# Base_4node_V2_0.net
KiCad netlist of a schematic drawn in EAGLE
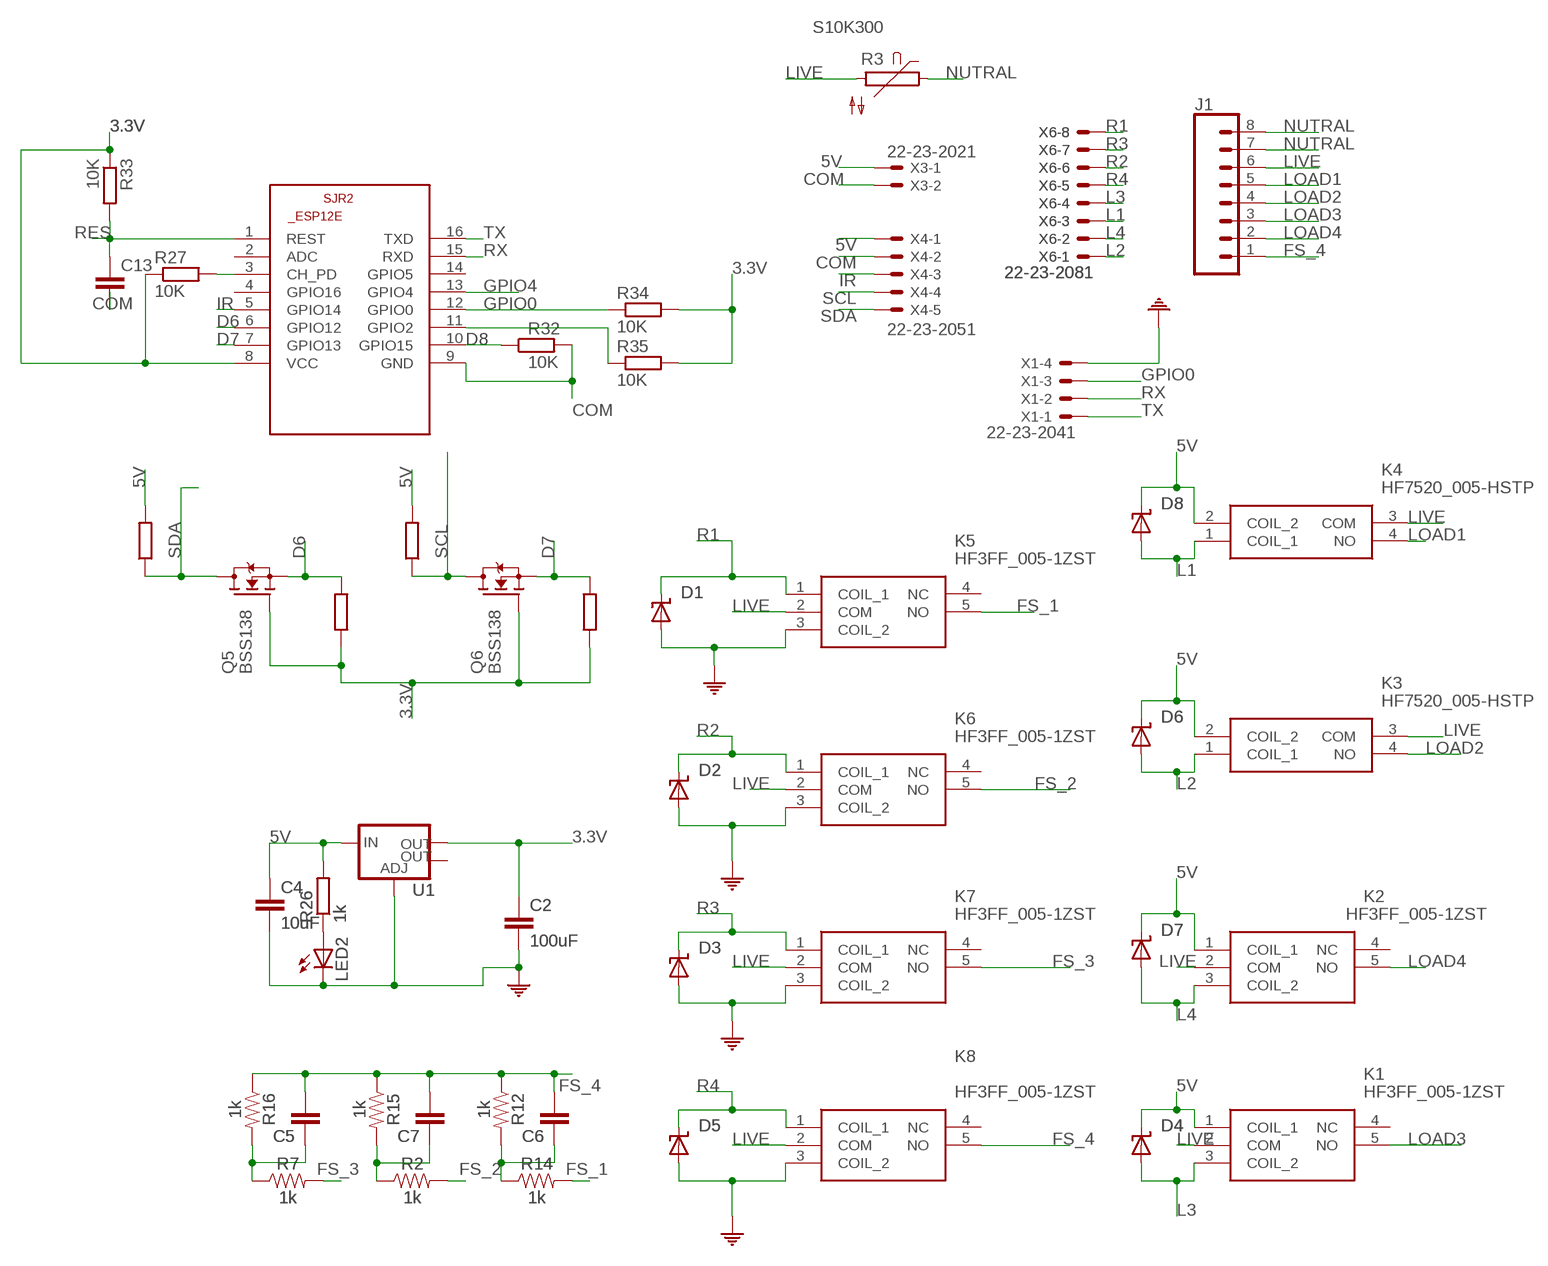
[diagram p0: schematic, sheet 1]

(export (version "E")
  (design (tool "Eeschema 10.0.6"))
  (components
    (comp (ref "C2")
      (value "100uF")
      (footprint "eagle-import:C1206")
      (libsource (lib "eagle-import") (part "C-EUC1206"))
    )
    (comp (ref "C4")
      (value "10uF")
      (footprint "eagle-import:C1206")
      (libsource (lib "eagle-import") (part "C-EUC1206"))
    )
    (comp (ref "C5")
      (value "C-EU275-134X316")
      (footprint "eagle-import:C275-134X316")
      (libsource (lib "eagle-import") (part "C-EU275-134X316"))
    )
    (comp (ref "C6")
      (value "C-EU275-093X316")
      (footprint "eagle-import:C275-093X316")
      (libsource (lib "eagle-import") (part "rcl-2_C-EU275-093X316"))
    )
    (comp (ref "C7")
      (value "C-EU275-113X316")
      (footprint "eagle-import:C275-113X316")
      (libsource (lib "eagle-import") (part "rcl-2_C-EU275-113X316"))
    )
    (comp (ref "C13")
      (value "C-EUC0805")
      (footprint "eagle-import:C0805")
      (libsource (lib "eagle-import") (part "rcl_334_C-EUC0805"))
    )
    (comp (ref "D1")
      (value "SUPPRESSOR-SMBJ")
      (footprint "eagle-import:SMBJ")
      (libsource (lib "eagle-import") (part "SUPPRESSOR-SMBJ"))
    )
    (comp (ref "D2")
      (value "SUPPRESSOR-SMBJ")
      (footprint "eagle-import:SMBJ")
      (libsource (lib "eagle-import") (part "SUPPRESSOR-SMBJ"))
    )
    (comp (ref "D3")
      (value "SUPPRESSOR-SMBJ")
      (footprint "eagle-import:SMBJ")
      (libsource (lib "eagle-import") (part "SUPPRESSOR-SMBJ"))
    )
    (comp (ref "D4")
      (value "SUPPRESSOR-SMBJ")
      (footprint "eagle-import:SMBJ")
      (libsource (lib "eagle-import") (part "SUPPRESSOR-SMBJ"))
    )
    (comp (ref "D5")
      (value "SUPPRESSOR-SMBJ")
      (footprint "eagle-import:SMBJ")
      (libsource (lib "eagle-import") (part "SUPPRESSOR-SMBJ"))
    )
    (comp (ref "D6")
      (value "SUPPRESSOR-SMBJ")
      (footprint "eagle-import:SMBJ")
      (libsource (lib "eagle-import") (part "SUPPRESSOR-SMBJ"))
    )
    (comp (ref "D7")
      (value "SUPPRESSOR-SMBJ")
      (footprint "eagle-import:SMBJ")
      (libsource (lib "eagle-import") (part "SUPPRESSOR-SMBJ"))
    )
    (comp (ref "D8")
      (value "SUPPRESSOR-SMBJ")
      (footprint "eagle-import:SMBJ")
      (libsource (lib "eagle-import") (part "SUPPRESSOR-SMBJ"))
    )
    (comp (ref "J1")
      (value "CONN_083.5MM-8")
      (footprint "eagle-import:SCREWTERMINAL-3.5MM-8")
      (libsource (lib "eagle-import") (part "CONN_083.5MM-8"))
    )
    (comp (ref "K1")
      (value "HF3FF_005-1ZST")
      (footprint "eagle-import:HF3FF0051ZST")
      (fields (field (name "ARROW_PART_NUMBER") "HF3FF/005-1ZST"))
      (libsource (lib "eagle-import") (part "HF3FF_005-1ZST"))
    )
    (comp (ref "K2")
      (value "HF3FF_005-1ZST")
      (footprint "eagle-import:HF3FF0051ZST")
      (fields (field (name "ARROW_PART_NUMBER") "HF3FF/005-1ZST"))
      (libsource (lib "eagle-import") (part "HF3FF_005-1ZST"))
    )
    (comp (ref "K3")
      (value "HF7520_005-HSTP")
      (footprint "eagle-import:HF7520005HSTP")
      (fields (field (name "ARROW_PART_NUMBER") "HF7520/005-HSTP"))
      (libsource (lib "eagle-import") (part "HF7520_005-HSTP"))
    )
    (comp (ref "K4")
      (value "HF7520_005-HSTP")
      (footprint "eagle-import:HF7520005HSTP")
      (fields (field (name "ARROW_PART_NUMBER") "HF7520/005-HSTP"))
      (libsource (lib "eagle-import") (part "HF7520_005-HSTP"))
    )
    (comp (ref "K5")
      (value "HF3FF_005-1ZST")
      (footprint "eagle-import:HF3FF0051ZST")
      (fields (field (name "ARROW_PART_NUMBER") "HF3FF/005-1ZST"))
      (libsource (lib "eagle-import") (part "HF3FF_005-1ZST"))
    )
    (comp (ref "K6")
      (value "HF3FF_005-1ZST")
      (footprint "eagle-import:HF3FF0051ZST")
      (fields (field (name "ARROW_PART_NUMBER") "HF3FF/005-1ZST"))
      (libsource (lib "eagle-import") (part "HF3FF_005-1ZST"))
    )
    (comp (ref "K7")
      (value "HF3FF_005-1ZST")
      (footprint "eagle-import:HF3FF0051ZST")
      (fields (field (name "ARROW_PART_NUMBER") "HF3FF/005-1ZST"))
      (libsource (lib "eagle-import") (part "HF3FF_005-1ZST"))
    )
    (comp (ref "K8")
      (value "HF3FF_005-1ZST")
      (footprint "eagle-import:HF3FF0051ZST")
      (fields (field (name "ARROW_PART_NUMBER") "HF3FF/005-1ZST"))
      (libsource (lib "eagle-import") (part "HF3FF_005-1ZST"))
    )
    (comp (ref "LED2")
      (value "LEDCHIPLED_1206")
      (footprint "eagle-import:CHIPLED_1206")
      (libsource (lib "eagle-import") (part "LEDCHIPLED_1206"))
    )
    (comp (ref "Q5")
      (value "BSS138")
      (footprint "eagle-import:SOT23")
      (fields (field (name "MF") "Fairchild"))
      (libsource (lib "eagle-import") (part "BSS138"))
    )
    (comp (ref "Q6")
      (value "BSS138")
      (footprint "eagle-import:SOT23")
      (fields (field (name "MF") "Fairchild"))
      (libsource (lib "eagle-import") (part "BSS138"))
    )
    (comp (ref "R2")
      (value "1k")
      (footprint "eagle-import:AXIAL-0.1")
      (libsource (lib "eagle-import") (part "1KOHM-VERT-1/4W-1%"))
    )
    (comp (ref "R3")
      (value "S10K300")
      (footprint "eagle-import:S10K300")
      (libsource (lib "eagle-import") (part "S10K300"))
    )
    (comp (ref "R7")
      (value "1k")
      (footprint "eagle-import:AXIAL-0.1")
      (libsource (lib "eagle-import") (part "1KOHM-VERT-1/4W-1%"))
    )
    (comp (ref "R12")
      (value "1k")
      (footprint "eagle-import:AXIAL-0.3")
      (libsource (lib "eagle-import") (part "SparkFun-Resistors1_1KOHM-HORIZ-1/4W-1%"))
    )
    (comp (ref "R14")
      (value "1k")
      (footprint "eagle-import:AXIAL-0.1")
      (libsource (lib "eagle-import") (part "1KOHM-VERT-1/4W-1%"))
    )
    (comp (ref "R15")
      (value "1k")
      (footprint "eagle-import:AXIAL-0.3")
      (libsource (lib "eagle-import") (part "SparkFun-Resistors1_1KOHM-HORIZ-1/4W-1%"))
    )
    (comp (ref "R16")
      (value "1k")
      (footprint "eagle-import:AXIAL-0.3")
      (libsource (lib "eagle-import") (part "SparkFun-Resistors1_1KOHM-HORIZ-1/4W-1%"))
    )
    (comp (ref "R26")
      (value "1k")
      (footprint "eagle-import:R0805")
      (libsource (lib "eagle-import") (part "R-EU_R0805"))
    )
    (comp (ref "R27")
      (value "10K")
      (footprint "eagle-import:R0805")
      (libsource (lib "eagle-import") (part "resistor_348_R-EU_R0805"))
    )
    (comp (ref "R32")
      (value "10K")
      (footprint "eagle-import:R0805")
      (libsource (lib "eagle-import") (part "resistor_348_R-EU_R0805"))
    )
    (comp (ref "R33")
      (value "10K")
      (footprint "eagle-import:R0805")
      (libsource (lib "eagle-import") (part "resistor_348_R-EU_R0805"))
    )
    (comp (ref "R34")
      (value "10K")
      (footprint "eagle-import:R0805")
      (libsource (lib "eagle-import") (part "resistor_348_R-EU_R0805"))
    )
    (comp (ref "R35")
      (value "10K")
      (footprint "eagle-import:R0805")
      (libsource (lib "eagle-import") (part "resistor_348_R-EU_R0805"))
    )
    (comp (ref "R36")
      (value "10K")
      (footprint "eagle-import:R0805")
      (libsource (lib "eagle-import") (part "resistor_348_R-EU_R0805"))
    )
    (comp (ref "R37")
      (value "10K")
      (footprint "eagle-import:R0805")
      (libsource (lib "eagle-import") (part "resistor_348_R-EU_R0805"))
    )
    (comp (ref "R38")
      (value "10K")
      (footprint "eagle-import:R0805")
      (libsource (lib "eagle-import") (part "resistor_348_R-EU_R0805"))
    )
    (comp (ref "R39")
      (value "10K")
      (footprint "eagle-import:R0805")
      (libsource (lib "eagle-import") (part "resistor_348_R-EU_R0805"))
    )
    (comp (ref "SJR2")
      (value "ESP8266-12EESP12E")
      (footprint "eagle-import:ESP8266-ESP12E")
      (libsource (lib "eagle-import") (part "ESP8266-12EESP12E"))
    )
    (comp (ref "U1")
      (value "V_REG_LM1117SOT223")
      (footprint "eagle-import:SOT223")
      (libsource (lib "eagle-import") (part "V_REG_LM1117SOT223"))
    )
    (comp (ref "X1")
      (value "22-23-2041")
      (footprint "eagle-import:22-23-2041")
      (libsource (lib "eagle-import") (part "22-23-2041"))
    )
    (comp (ref "X3")
      (value "22-23-2021")
      (footprint "eagle-import:22-23-2021")
      (libsource (lib "eagle-import") (part "22-23-2021"))
    )
    (comp (ref "X4")
      (value "22-23-2051")
      (footprint "eagle-import:22-23-2051")
      (libsource (lib "eagle-import") (part "22-23-2051"))
    )
    (comp (ref "X6")
      (value "22-23-2081")
      (footprint "eagle-import:22-23-2081")
      (libsource (lib "eagle-import") (part "22-23-2081"))
    )
  )
  (nets
    (net (code "1") (name "/3.3V") (class "Default")
      (node (ref "C2") (pin "1") (pinfunction "1_1") (pintype "passive"))
      (node (ref "Q5") (pin "1") (pinfunction "G_1") (pintype "passive"))
      (node (ref "Q6") (pin "1") (pinfunction "G_1") (pintype "passive"))
      (node (ref "R27") (pin "1") (pinfunction "1_1") (pintype "passive"))
      (node (ref "R33") (pin "1") (pinfunction "1_1") (pintype "passive"))
      (node (ref "R34") (pin "2") (pinfunction "2_2") (pintype "passive"))
      (node (ref "R35") (pin "2") (pinfunction "2_2") (pintype "passive"))
      (node (ref "R37") (pin "2") (pinfunction "2_2") (pintype "passive"))
      (node (ref "R39") (pin "2") (pinfunction "2_2") (pintype "passive"))
      (node (ref "SJR2") (pin "8") (pinfunction "VCC_8") (pintype "bidirectional"))
      (node (ref "U1") (pin "2") (pinfunction "OUT_2") (pintype "output"))
    )
    (net (code "2") (name "/5V") (class "Default")
      (node (ref "C4") (pin "1") (pinfunction "1_1") (pintype "passive"))
      (node (ref "D4") (pin "C") (pinfunction "C_C") (pintype "passive"))
      (node (ref "D6") (pin "C") (pinfunction "C_C") (pintype "passive"))
      (node (ref "D7") (pin "C") (pinfunction "C_C") (pintype "passive"))
      (node (ref "D8") (pin "C") (pinfunction "C_C") (pintype "passive"))
      (node (ref "K1") (pin "1") (pinfunction "COIL_1_1") (pintype "bidirectional"))
      (node (ref "K2") (pin "1") (pinfunction "COIL_1_1") (pintype "bidirectional"))
      (node (ref "K3") (pin "2") (pinfunction "COIL_2_2") (pintype "bidirectional"))
      (node (ref "K4") (pin "2") (pinfunction "COIL_2_2") (pintype "bidirectional"))
      (node (ref "R26") (pin "2") (pinfunction "2_2") (pintype "passive"))
      (node (ref "R36") (pin "2") (pinfunction "2_2") (pintype "passive"))
      (node (ref "R38") (pin "2") (pinfunction "2_2") (pintype "passive"))
      (node (ref "U1") (pin "3") (pinfunction "IN_3") (pintype "input"))
      (node (ref "X3") (pin "1") (pinfunction "S_1") (pintype "passive"))
      (node (ref "X4") (pin "1") (pinfunction "S_1") (pintype "passive"))
    )
    (net (code "3") (name "/D6") (class "Default")
      (node (ref "Q5") (pin "2") (pinfunction "S_2") (pintype "passive"))
      (node (ref "R37") (pin "1") (pinfunction "1_1") (pintype "passive"))
      (node (ref "SJR2") (pin "6") (pinfunction "GPIO12_6") (pintype "bidirectional"))
    )
    (net (code "4") (name "/D7") (class "Default")
      (node (ref "Q6") (pin "2") (pinfunction "S_2") (pintype "passive"))
      (node (ref "R39") (pin "1") (pinfunction "1_1") (pintype "passive"))
      (node (ref "SJR2") (pin "7") (pinfunction "GPIO13_7") (pintype "bidirectional"))
    )
    (net (code "5") (name "/D8") (class "Default")
      (node (ref "R32") (pin "1") (pinfunction "1_1") (pintype "passive"))
      (node (ref "SJR2") (pin "10") (pinfunction "GPIO15_10") (pintype "bidirectional"))
    )
    (net (code "6") (name "/FS_1") (class "Default")
      (node (ref "K5") (pin "5") (pinfunction "NO_5") (pintype "bidirectional"))
      (node (ref "R14") (pin "P$2") (pinfunction "2_P$2") (pintype "passive"))
    )
    (net (code "7") (name "/FS_2") (class "Default")
      (node (ref "K6") (pin "5") (pinfunction "NO_5") (pintype "bidirectional"))
      (node (ref "R2") (pin "P$2") (pinfunction "2_P$2") (pintype "passive"))
    )
    (net (code "8") (name "/FS_3") (class "Default")
      (node (ref "K7") (pin "5") (pinfunction "NO_5") (pintype "bidirectional"))
      (node (ref "R7") (pin "P$2") (pinfunction "2_P$2") (pintype "passive"))
    )
    (net (code "9") (name "/FS_4") (class "Default")
      (node (ref "C5") (pin "2") (pinfunction "2_2") (pintype "passive"))
      (node (ref "C6") (pin "2") (pinfunction "2_2") (pintype "passive"))
      (node (ref "C7") (pin "2") (pinfunction "2_2") (pintype "passive"))
      (node (ref "J1") (pin "1") (pinfunction "1_1") (pintype "passive"))
      (node (ref "K8") (pin "5") (pinfunction "NO_5") (pintype "bidirectional"))
      (node (ref "R12") (pin "P$1") (pinfunction "1_P$1") (pintype "passive"))
      (node (ref "R15") (pin "P$1") (pinfunction "1_P$1") (pintype "passive"))
      (node (ref "R16") (pin "P$1") (pinfunction "1_P$1") (pintype "passive"))
    )
    (net (code "10") (name "/GPIO0") (class "Default")
      (node (ref "R34") (pin "1") (pinfunction "1_1") (pintype "passive"))
      (node (ref "SJR2") (pin "12") (pinfunction "GPIO0_12") (pintype "bidirectional"))
      (node (ref "X1") (pin "3") (pinfunction "S_3") (pintype "passive"))
    )
    (net (code "11") (name "/GPIO4") (class "Default")
      (node (ref "SJR2") (pin "13") (pinfunction "GPIO4_13") (pintype "bidirectional"))
    )
    (net (code "12") (name "/IR") (class "Default")
      (node (ref "SJR2") (pin "5") (pinfunction "GPIO14_5") (pintype "bidirectional"))
      (node (ref "X4") (pin "3") (pinfunction "S_3") (pintype "passive"))
    )
    (net (code "13") (name "/L1") (class "Default")
      (node (ref "D8") (pin "A") (pinfunction "A_A") (pintype "passive"))
      (node (ref "K4") (pin "1") (pinfunction "COIL_1_1") (pintype "bidirectional"))
      (node (ref "X6") (pin "3") (pinfunction "S_3") (pintype "passive"))
    )
    (net (code "14") (name "/L2") (class "Default")
      (node (ref "D6") (pin "A") (pinfunction "A_A") (pintype "passive"))
      (node (ref "K3") (pin "1") (pinfunction "COIL_1_1") (pintype "bidirectional"))
      (node (ref "X6") (pin "1") (pinfunction "S_1") (pintype "passive"))
    )
    (net (code "15") (name "/L3") (class "Default")
      (node (ref "D4") (pin "A") (pinfunction "A_A") (pintype "passive"))
      (node (ref "K1") (pin "3") (pinfunction "COIL_2_3") (pintype "bidirectional"))
      (node (ref "X6") (pin "4") (pinfunction "S_4") (pintype "passive"))
    )
    (net (code "16") (name "/L4") (class "Default")
      (node (ref "D7") (pin "A") (pinfunction "A_A") (pintype "passive"))
      (node (ref "K2") (pin "3") (pinfunction "COIL_2_3") (pintype "bidirectional"))
      (node (ref "X6") (pin "2") (pinfunction "S_2") (pintype "passive"))
    )
    (net (code "17") (name "/LIVE") (class "Default")
      (node (ref "J1") (pin "6") (pinfunction "6_6") (pintype "passive"))
      (node (ref "K1") (pin "2") (pinfunction "COM_2") (pintype "bidirectional"))
      (node (ref "K2") (pin "2") (pinfunction "COM_2") (pintype "bidirectional"))
      (node (ref "K3") (pin "3") (pinfunction "COM_3") (pintype "bidirectional"))
      (node (ref "K4") (pin "3") (pinfunction "COM_3") (pintype "bidirectional"))
      (node (ref "K5") (pin "2") (pinfunction "COM_2") (pintype "bidirectional"))
      (node (ref "K6") (pin "2") (pinfunction "COM_2") (pintype "bidirectional"))
      (node (ref "K7") (pin "2") (pinfunction "COM_2") (pintype "bidirectional"))
      (node (ref "K8") (pin "2") (pinfunction "COM_2") (pintype "bidirectional"))
      (node (ref "R3") (pin "2") (pinfunction "2_2") (pintype "passive"))
    )
    (net (code "18") (name "/LOAD1") (class "Default")
      (node (ref "J1") (pin "5") (pinfunction "5_5") (pintype "passive"))
      (node (ref "K4") (pin "4") (pinfunction "NO_4") (pintype "bidirectional"))
    )
    (net (code "19") (name "/LOAD2") (class "Default")
      (node (ref "J1") (pin "4") (pinfunction "4_4") (pintype "passive"))
      (node (ref "K3") (pin "4") (pinfunction "NO_4") (pintype "bidirectional"))
    )
    (net (code "20") (name "/LOAD3") (class "Default")
      (node (ref "J1") (pin "3") (pinfunction "3_3") (pintype "passive"))
      (node (ref "K1") (pin "5") (pinfunction "NO_5") (pintype "bidirectional"))
    )
    (net (code "21") (name "/LOAD4") (class "Default")
      (node (ref "J1") (pin "2") (pinfunction "2_2") (pintype "passive"))
      (node (ref "K2") (pin "5") (pinfunction "NO_5") (pintype "bidirectional"))
    )
    (net (code "22") (name "/NUTRAL") (class "Default")
      (node (ref "J1") (pin "7") (pinfunction "7_7") (pintype "passive"))
      (node (ref "J1") (pin "8") (pinfunction "8_8") (pintype "passive"))
      (node (ref "R3") (pin "1") (pinfunction "1_1") (pintype "passive"))
    )
    (net (code "23") (name "/R1") (class "Default")
      (node (ref "D1") (pin "C") (pinfunction "C_C") (pintype "passive"))
      (node (ref "K5") (pin "1") (pinfunction "COIL_1_1") (pintype "bidirectional"))
      (node (ref "X6") (pin "8") (pinfunction "S_8") (pintype "passive"))
    )
    (net (code "24") (name "/R2") (class "Default")
      (node (ref "D2") (pin "C") (pinfunction "C_C") (pintype "passive"))
      (node (ref "K6") (pin "1") (pinfunction "COIL_1_1") (pintype "bidirectional"))
      (node (ref "X6") (pin "6") (pinfunction "S_6") (pintype "passive"))
    )
    (net (code "25") (name "/R3") (class "Default")
      (node (ref "D3") (pin "C") (pinfunction "C_C") (pintype "passive"))
      (node (ref "K7") (pin "1") (pinfunction "COIL_1_1") (pintype "bidirectional"))
      (node (ref "X6") (pin "7") (pinfunction "S_7") (pintype "passive"))
    )
    (net (code "26") (name "/R4") (class "Default")
      (node (ref "D5") (pin "C") (pinfunction "C_C") (pintype "passive"))
      (node (ref "K8") (pin "1") (pinfunction "COIL_1_1") (pintype "bidirectional"))
      (node (ref "X6") (pin "5") (pinfunction "S_5") (pintype "passive"))
    )
    (net (code "27") (name "/RES") (class "Default")
      (node (ref "C13") (pin "1") (pinfunction "1_1") (pintype "passive"))
      (node (ref "R33") (pin "2") (pinfunction "2_2") (pintype "passive"))
      (node (ref "SJR2") (pin "1") (pinfunction "REST_1") (pintype "bidirectional"))
    )
    (net (code "28") (name "/RX") (class "Default")
      (node (ref "SJR2") (pin "15") (pinfunction "RXD_15") (pintype "bidirectional"))
      (node (ref "X1") (pin "2") (pinfunction "S_2") (pintype "passive"))
    )
    (net (code "29") (name "/SCL") (class "Default")
      (node (ref "Q6") (pin "3") (pinfunction "D_3") (pintype "passive"))
      (node (ref "R36") (pin "1") (pinfunction "1_1") (pintype "passive"))
      (node (ref "X4") (pin "4") (pinfunction "S_4") (pintype "passive"))
    )
    (net (code "30") (name "/SDA") (class "Default")
      (node (ref "Q5") (pin "3") (pinfunction "D_3") (pintype "passive"))
      (node (ref "R38") (pin "1") (pinfunction "1_1") (pintype "passive"))
      (node (ref "X4") (pin "5") (pinfunction "S_5") (pintype "passive"))
    )
    (net (code "31") (name "/TX") (class "Default")
      (node (ref "SJR2") (pin "16") (pinfunction "TXD_16") (pintype "bidirectional"))
      (node (ref "X1") (pin "1") (pinfunction "S_1") (pintype "passive"))
    )
    (net (code "32") (name "COM") (class "Default")
      (node (ref "C13") (pin "2") (pinfunction "2_2") (pintype "passive"))
      (node (ref "C2") (pin "2") (pinfunction "2_2") (pintype "passive"))
      (node (ref "C4") (pin "2") (pinfunction "2_2") (pintype "passive"))
      (node (ref "D1") (pin "A") (pinfunction "A_A") (pintype "passive"))
      (node (ref "D2") (pin "A") (pinfunction "A_A") (pintype "passive"))
      (node (ref "D3") (pin "A") (pinfunction "A_A") (pintype "passive"))
      (node (ref "D5") (pin "A") (pinfunction "A_A") (pintype "passive"))
      (node (ref "K5") (pin "3") (pinfunction "COIL_2_3") (pintype "bidirectional"))
      (node (ref "K6") (pin "3") (pinfunction "COIL_2_3") (pintype "bidirectional"))
      (node (ref "K7") (pin "3") (pinfunction "COIL_2_3") (pintype "bidirectional"))
      (node (ref "K8") (pin "3") (pinfunction "COIL_2_3") (pintype "bidirectional"))
      (node (ref "LED2") (pin "C") (pinfunction "C_C") (pintype "passive"))
      (node (ref "R32") (pin "2") (pinfunction "2_2") (pintype "passive"))
      (node (ref "SJR2") (pin "9") (pinfunction "GND_9") (pintype "bidirectional"))
      (node (ref "U1") (pin "1") (pinfunction "ADJ_1") (pintype "input"))
      (node (ref "X1") (pin "4") (pinfunction "S_4") (pintype "passive"))
      (node (ref "X3") (pin "2") (pinfunction "S_2") (pintype "passive"))
      (node (ref "X4") (pin "2") (pinfunction "S_2") (pintype "passive"))
    )
    (net (code "33") (name "Net-(LED2-PadA)") (class "Default")
      (node (ref "LED2") (pin "A") (pinfunction "A_A") (pintype "passive"))
      (node (ref "R26") (pin "1") (pinfunction "1_1") (pintype "passive"))
    )
    (net (code "34") (name "Net-(R12-2)") (class "Default")
      (node (ref "C6") (pin "1") (pinfunction "1_1") (pintype "passive"))
      (node (ref "R12") (pin "P$2") (pinfunction "2_P$2") (pintype "passive"))
      (node (ref "R14") (pin "P$1") (pinfunction "1_P$1") (pintype "passive"))
    )
    (net (code "35") (name "Net-(R15-2)") (class "Default")
      (node (ref "C7") (pin "1") (pinfunction "1_1") (pintype "passive"))
      (node (ref "R15") (pin "P$2") (pinfunction "2_P$2") (pintype "passive"))
      (node (ref "R2") (pin "P$1") (pinfunction "1_P$1") (pintype "passive"))
    )
    (net (code "36") (name "Net-(R16-2)") (class "Default")
      (node (ref "C5") (pin "1") (pinfunction "1_1") (pintype "passive"))
      (node (ref "R16") (pin "P$2") (pinfunction "2_P$2") (pintype "passive"))
      (node (ref "R7") (pin "P$1") (pinfunction "1_P$1") (pintype "passive"))
    )
    (net (code "37") (name "Net-(SJR2-CH_PD)") (class "Default")
      (node (ref "R27") (pin "2") (pinfunction "2_2") (pintype "passive"))
      (node (ref "SJR2") (pin "3") (pinfunction "CH_PD_3") (pintype "bidirectional"))
    )
    (net (code "38") (name "Net-(SJR2-GPIO2)") (class "Default")
      (node (ref "R35") (pin "1") (pinfunction "1_1") (pintype "passive"))
      (node (ref "SJR2") (pin "11") (pinfunction "GPIO2_11") (pintype "bidirectional"))
    )
    (net (code "39") (name "unconnected-(K1-NC-Pad4)") (class "Default")
      (node (ref "K1") (pin "4") (pinfunction "NC_4") (pintype "no_connect"))
    )
    (net (code "40") (name "unconnected-(K2-NC-Pad4)") (class "Default")
      (node (ref "K2") (pin "4") (pinfunction "NC_4") (pintype "no_connect"))
    )
    (net (code "41") (name "unconnected-(K5-NC-Pad4)") (class "Default")
      (node (ref "K5") (pin "4") (pinfunction "NC_4") (pintype "no_connect"))
    )
    (net (code "42") (name "unconnected-(K6-NC-Pad4)") (class "Default")
      (node (ref "K6") (pin "4") (pinfunction "NC_4") (pintype "no_connect"))
    )
    (net (code "43") (name "unconnected-(K7-NC-Pad4)") (class "Default")
      (node (ref "K7") (pin "4") (pinfunction "NC_4") (pintype "no_connect"))
    )
    (net (code "44") (name "unconnected-(K8-NC-Pad4)") (class "Default")
      (node (ref "K8") (pin "4") (pinfunction "NC_4") (pintype "no_connect"))
    )
    (net (code "45") (name "unconnected-(SJR2-ADC-Pad2)") (class "Default")
      (node (ref "SJR2") (pin "2") (pinfunction "ADC_2") (pintype "bidirectional"))
    )
    (net (code "46") (name "unconnected-(SJR2-GPIO5-Pad14)") (class "Default")
      (node (ref "SJR2") (pin "14") (pinfunction "GPIO5_14") (pintype "bidirectional"))
    )
    (net (code "47") (name "unconnected-(SJR2-GPIO16-Pad4)") (class "Default")
      (node (ref "SJR2") (pin "4") (pinfunction "GPIO16_4") (pintype "bidirectional"))
    )
    (net (code "48") (name "unconnected-(U1-OUT-Pad4)") (class "Default")
      (node (ref "U1") (pin "4") (pinfunction "OUT_4") (pintype "output"))
    )
  )
)
